# overallPCB.net
KiCad netlist of a schematic drawn in EAGLE
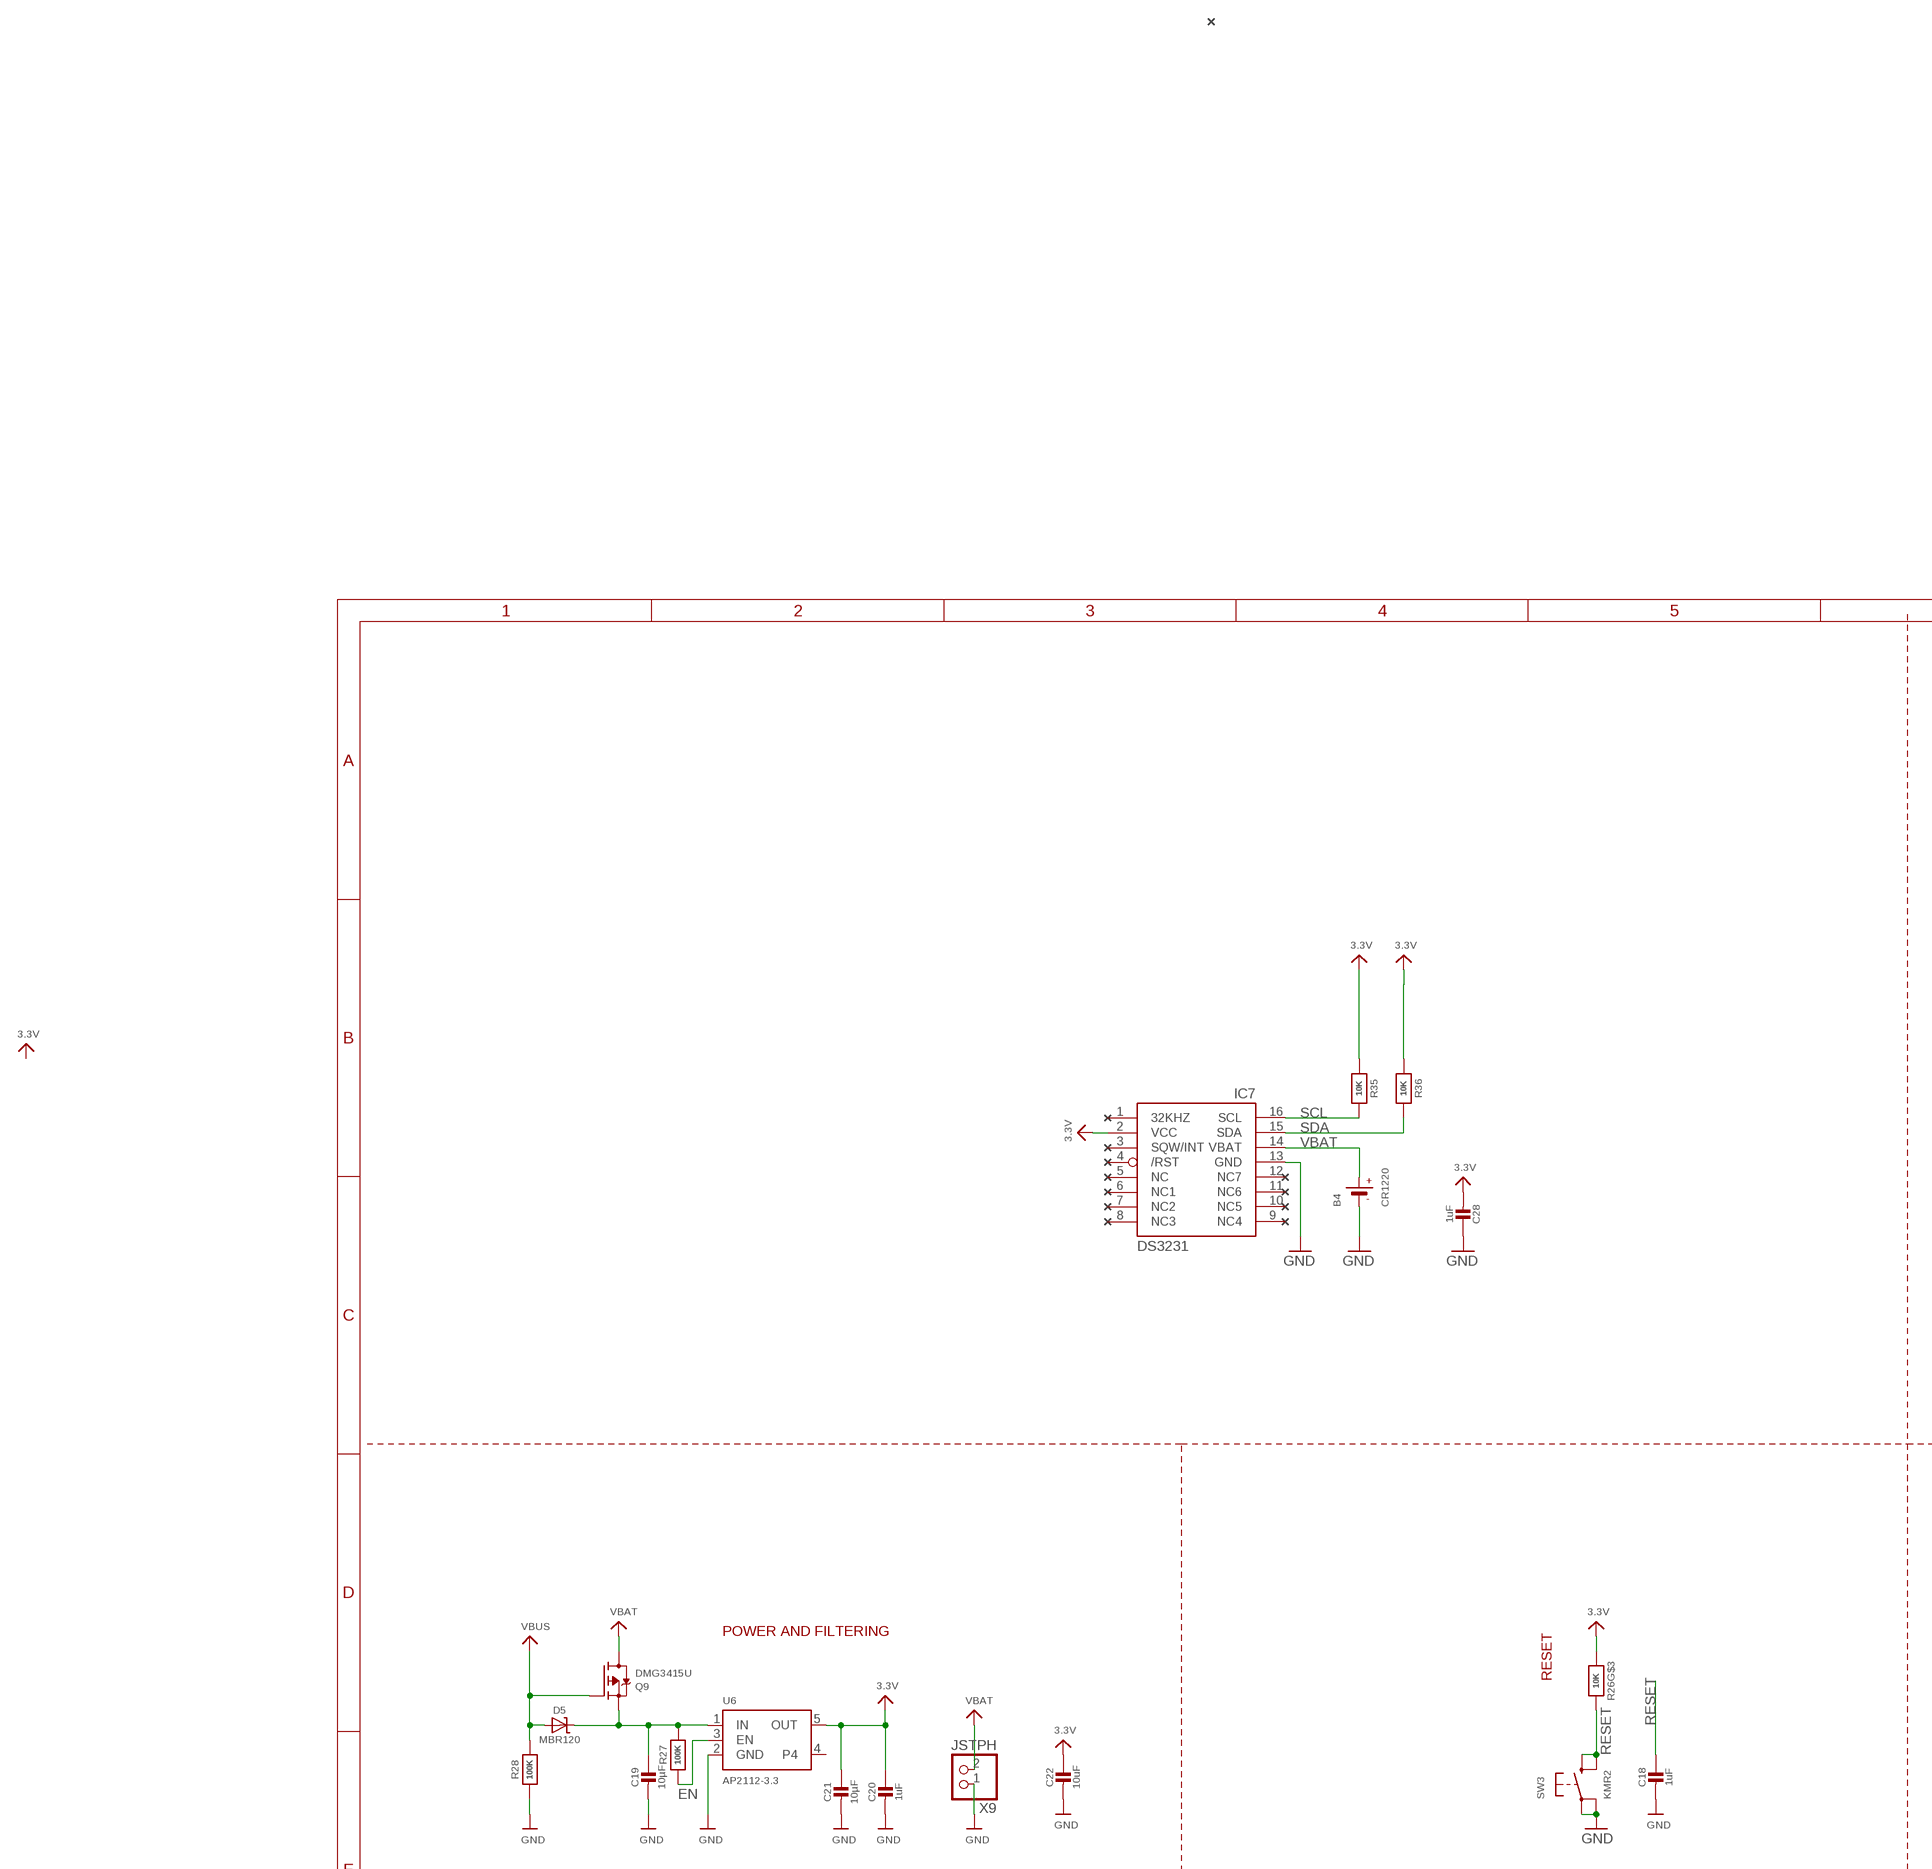
[diagram p0: schematic, sheet 1, part 1 of 3]
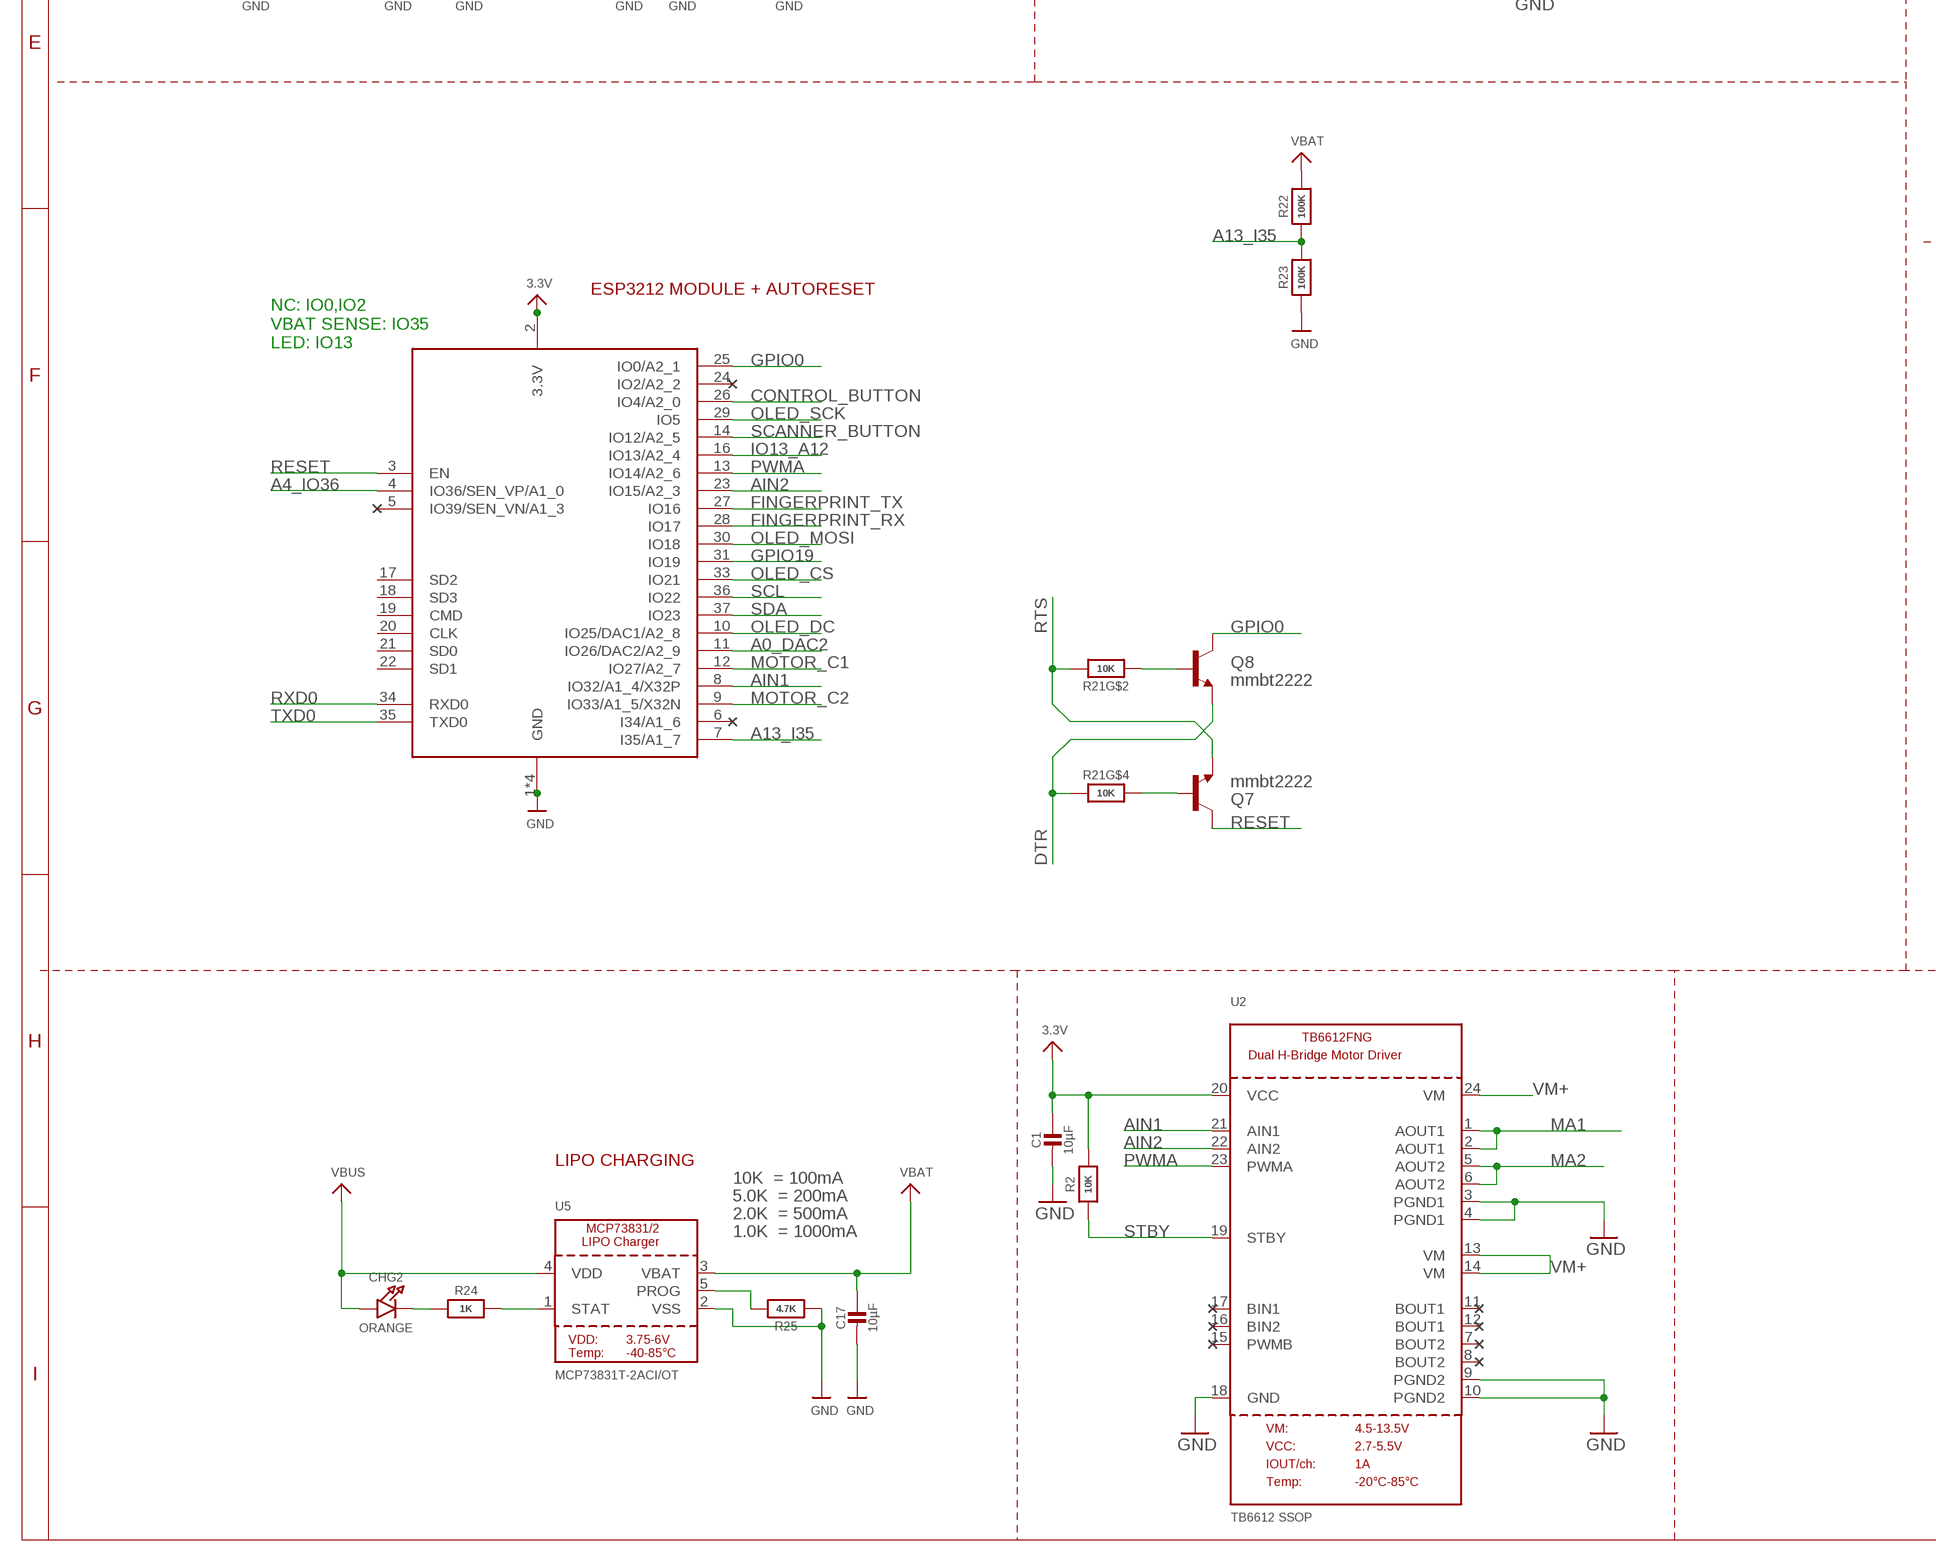
[diagram p1: schematic, sheet 1, part 2 of 3]
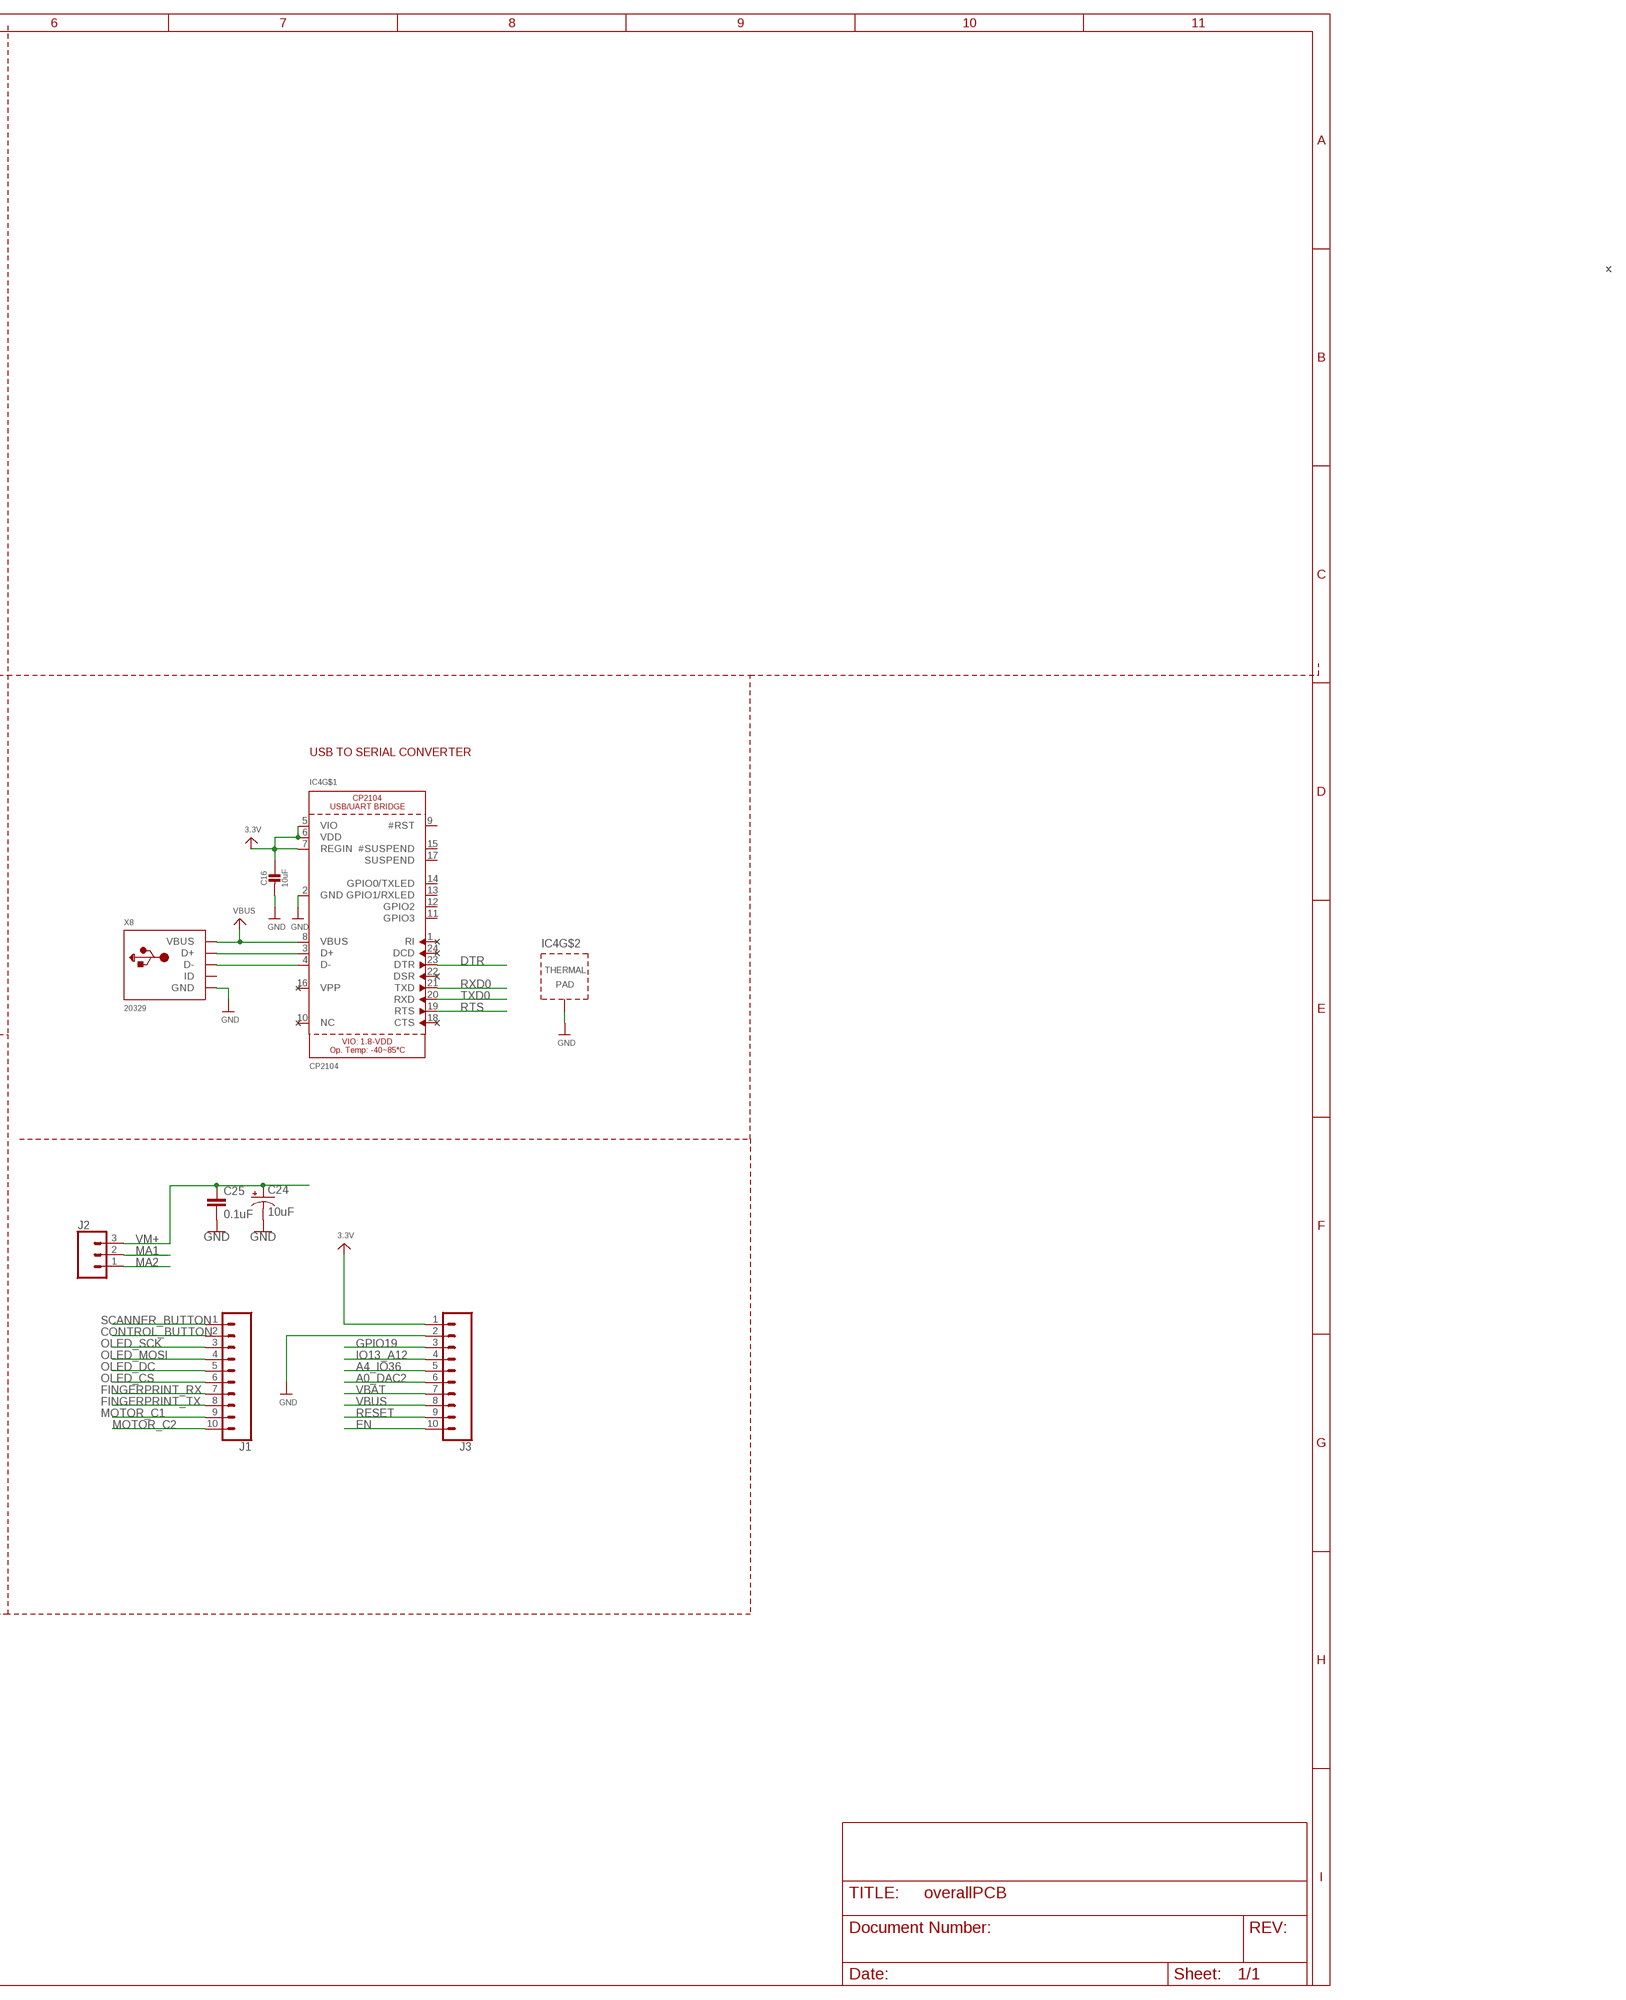
[diagram p2: schematic, sheet 1, part 3 of 3]

(export (version "E")
  (design (tool "Eeschema 10.0.6"))
  (components
    (comp (ref "B4")
      (value "CR1220")
      (footprint "eagle-import:CR1220")
      (libsource (lib "eagle-import") (part "BATTERYCR1220_SMT"))
    )
    (comp (ref "C1")
      (value "10µF")
      (footprint "eagle-import:0805-NO")
      (libsource (lib "eagle-import") (part "CAP_CERAMIC0805-NOOUTLINE"))
    )
    (comp (ref "C16")
      (value "10uF")
      (footprint "eagle-import:0805-NO")
      (libsource (lib "eagle-import") (part "CAP_CERAMIC0805-NOOUTLINE"))
    )
    (comp (ref "C17")
      (value "10µF")
      (footprint "eagle-import:0805-NO")
      (libsource (lib "eagle-import") (part "CAP_CERAMIC0805-NOOUTLINE"))
    )
    (comp (ref "C18")
      (value "1uF")
      (footprint "eagle-import:0603-NO")
      (libsource (lib "eagle-import") (part "CAP_CERAMIC0603_NO"))
    )
    (comp (ref "C19")
      (value "10µF")
      (footprint "eagle-import:0805-NO")
      (libsource (lib "eagle-import") (part "CAP_CERAMIC0805-NOOUTLINE"))
    )
    (comp (ref "C20")
      (value "1uF")
      (footprint "eagle-import:0603-NO")
      (libsource (lib "eagle-import") (part "CAP_CERAMIC0603_NO"))
    )
    (comp (ref "C21")
      (value "10µF")
      (footprint "eagle-import:0805-NO")
      (libsource (lib "eagle-import") (part "CAP_CERAMIC0805-NOOUTLINE"))
    )
    (comp (ref "C22")
      (value "10uF")
      (footprint "eagle-import:0805-NO")
      (libsource (lib "eagle-import") (part "CAP_CERAMIC0805-NOOUTLINE"))
    )
    (comp (ref "C24")
      (value "10uF")
      (footprint "eagle-import:EIA3216")
      (libsource (lib "eagle-import") (part "10UF-POLAR-EIA3216-16V-10%(TANT)"))
    )
    (comp (ref "C25")
      (value "0.1uF")
      (footprint "eagle-import:0402")
      (libsource (lib "eagle-import") (part "0.1UF-0402-16V-10%"))
    )
    (comp (ref "C28")
      (value "1uF")
      (footprint "eagle-import:0805-NO")
      (libsource (lib "eagle-import") (part "CAP_CERAMIC0805-NOOUTLINE"))
    )
    (comp (ref "CHG2")
      (value "ORANGE")
      (footprint "eagle-import:CHIPLED_0805_NOOUTLINE")
      (libsource (lib "eagle-import") (part "LED0805_NOOUTLINE"))
    )
    (comp (ref "D5")
      (value "MBR120")
      (footprint "eagle-import:SOD-123")
      (libsource (lib "eagle-import") (part "DIODE-SCHOTTKYSOD-123"))
    )
    (comp (ref "IC4")
      (value "CP2104")
      (footprint "eagle-import:QFN24_4MM_SMSC")
      (libsource (lib "eagle-import") (part "CP2104"))
    )
    (comp (ref "IC7")
      (value "DS3231/SO")
      (footprint "eagle-import:SO16W")
      (libsource (lib "eagle-import") (part "DS3231/SO"))
    )
    (comp (ref "J1")
      (value "CONN_10\"")
      (footprint "eagle-import:1X10")
      (libsource (lib "eagle-import") (part "CONN_10{dblquote}"))
    )
    (comp (ref "J2")
      (value "CONN_03POGO_PIN_HOLES_ONLY")
      (footprint "eagle-import:1X03_PP_HOLES_ONLY")
      (libsource (lib "eagle-import") (part "CONN_03POGO_PIN_HOLES_ONLY"))
    )
    (comp (ref "J3")
      (value "CONN_10\"")
      (footprint "eagle-import:1X10")
      (libsource (lib "eagle-import") (part "CONN_10{dblquote}"))
    )
    (comp (ref "Q7")
      (value "mmbt2222")
      (footprint "eagle-import:SOT23-3")
      (libsource (lib "eagle-import") (part "TRANSISTOR_NPNSOT23-3"))
    )
    (comp (ref "Q8")
      (value "mmbt2222")
      (footprint "eagle-import:SOT23-3")
      (libsource (lib "eagle-import") (part "TRANSISTOR_NPNSOT23-3"))
    )
    (comp (ref "Q9")
      (value "DMG3415U")
      (footprint "eagle-import:SOT23-R")
      (libsource (lib "eagle-import") (part "MOSFET-P"))
    )
    (comp (ref "R2")
      (value "10K")
      (footprint "eagle-import:0805-NO")
      (libsource (lib "eagle-import") (part "RESISTOR0805_NOOUTLINE"))
    )
    (comp (ref "R21")
      (value "10K")
      (footprint "eagle-import:RESPACK_4X0603")
      (libsource (lib "eagle-import") (part "RESISTOR_4PACK"))
    )
    (comp (ref "R22")
      (value "100K")
      (footprint "eagle-import:0603-NO")
      (libsource (lib "eagle-import") (part "RESISTOR_0603_NOOUT"))
    )
    (comp (ref "R23")
      (value "100K")
      (footprint "eagle-import:0603-NO")
      (libsource (lib "eagle-import") (part "RESISTOR_0603_NOOUT"))
    )
    (comp (ref "R24")
      (value "1K")
      (footprint "eagle-import:0603-NO")
      (libsource (lib "eagle-import") (part "RESISTOR_0603_NOOUT"))
    )
    (comp (ref "R25")
      (value "4.7K")
      (footprint "eagle-import:0603-NO")
      (libsource (lib "eagle-import") (part "RESISTOR_0603_NOOUT"))
    )
    (comp (ref "R26")
      (value "10K")
      (footprint "eagle-import:RESPACK_4X0603")
      (libsource (lib "eagle-import") (part "RESISTOR_4PACK"))
    )
    (comp (ref "R27")
      (value "100K")
      (footprint "eagle-import:0603-NO")
      (libsource (lib "eagle-import") (part "RESISTOR_0603_NOOUT"))
    )
    (comp (ref "R28")
      (value "100K")
      (footprint "eagle-import:0603-NO")
      (libsource (lib "eagle-import") (part "RESISTOR_0603_NOOUT"))
    )
    (comp (ref "R35")
      (value "10K")
      (footprint "eagle-import:0805-NO")
      (libsource (lib "eagle-import") (part "RESISTOR0805_NOOUTLINE"))
    )
    (comp (ref "R36")
      (value "10K")
      (footprint "eagle-import:0805-NO")
      (libsource (lib "eagle-import") (part "RESISTOR0805_NOOUTLINE"))
    )
    (comp (ref "SW3")
      (value "KMR2")
      (footprint "eagle-import:BTN_KMR2_4.6X2.8")
      (libsource (lib "eagle-import") (part "SWITCH_TACT_SMT4.6X2.8"))
    )
    (comp (ref "U2")
      (value "TB6612 SSOP")
      (footprint "eagle-import:SSOP24")
      (libsource (lib "eagle-import") (part "TB6612FNGSSOP"))
    )
    (comp (ref "U5")
      (value "MCP73831T-2ACI/OT")
      (footprint "eagle-import:SOT23-5")
      (libsource (lib "eagle-import") (part "MCP73831/2"))
    )
    (comp (ref "U6")
      (value "AP2112-3.3")
      (footprint "eagle-import:SOT23-5")
      (libsource (lib "eagle-import") (part "VREG_SOT23-5"))
    )
    (comp (ref "X7")
      (value "ESP32_WROOM32_SKINNY")
      (footprint "eagle-import:WROOM32_SKINNY")
      (libsource (lib "eagle-import") (part "ESP32_WROOM32_SKINNY"))
    )
    (comp (ref "X8")
      (value "20329")
      (footprint "eagle-import:4UCONN_20329_V2")
      (libsource (lib "eagle-import") (part "USB_MICRO_20329_V2"))
    )
    (comp (ref "X9")
      (value "JSTPH")
      (footprint "eagle-import:JSTPH2")
      (libsource (lib "eagle-import") (part "CON_JST_PH_2PIN"))
    )
  )
  (nets
    (net (code "1") (name "/A0_DAC2") (class "Default")
      (node (ref "J3") (pin "6") (pinfunction "6_6") (pintype "passive"))
      (node (ref "X7") (pin "11") (pinfunction "IO26/DAC2/A2_9_11") (pintype "bidirectional"))
    )
    (net (code "2") (name "/A4_IO36") (class "Default")
      (node (ref "J3") (pin "5") (pinfunction "5_5") (pintype "passive"))
      (node (ref "X7") (pin "4") (pinfunction "IO36/SEN_VP/A1_0_4") (pintype "passive"))
    )
    (net (code "3") (name "/A13_I35") (class "Default")
      (node (ref "R22") (pin "1") (pinfunction "1_1") (pintype "passive"))
      (node (ref "R23") (pin "2") (pinfunction "2_2") (pintype "passive"))
      (node (ref "X7") (pin "7") (pinfunction "I35/A1_7_7") (pintype "bidirectional"))
    )
    (net (code "4") (name "/AIN1") (class "Default")
      (node (ref "U2") (pin "21") (pinfunction "AIN1_21") (pintype "input"))
      (node (ref "X7") (pin "8") (pinfunction "IO32/A1_4/X32P_8") (pintype "bidirectional"))
    )
    (net (code "5") (name "/AIN2") (class "Default")
      (node (ref "U2") (pin "22") (pinfunction "AIN2_22") (pintype "input"))
      (node (ref "X7") (pin "23") (pinfunction "IO15/A2_3_23") (pintype "bidirectional"))
    )
    (net (code "6") (name "/CONTROL_BUTTON") (class "Default")
      (node (ref "J1") (pin "2") (pinfunction "2_2") (pintype "passive"))
      (node (ref "X7") (pin "26") (pinfunction "IO4/A2_0_26") (pintype "bidirectional"))
    )
    (net (code "7") (name "/DTR") (class "Default")
      (node (ref "IC4") (pin "23") (pinfunction "DTR_23") (pintype "output"))
      (node (ref "Q8") (pin "2") (pinfunction "E_2") (pintype "passive"))
      (node (ref "R21") (pin "4") (pinfunction "1_4") (pintype "passive"))
    )
    (net (code "8") (name "/EN") (class "Default")
      (node (ref "J3") (pin "10") (pinfunction "10_10") (pintype "passive"))
      (node (ref "R27") (pin "1") (pinfunction "1_1") (pintype "passive"))
      (node (ref "U6") (pin "3") (pinfunction "EN_3") (pintype "input"))
    )
    (net (code "9") (name "/FINGERPRINT_RX") (class "Default")
      (node (ref "J1") (pin "7") (pinfunction "7_7") (pintype "passive"))
      (node (ref "X7") (pin "28") (pinfunction "IO17_28") (pintype "bidirectional"))
    )
    (net (code "10") (name "/FINGERPRINT_TX") (class "Default")
      (node (ref "J1") (pin "8") (pinfunction "8_8") (pintype "passive"))
      (node (ref "X7") (pin "27") (pinfunction "IO16_27") (pintype "bidirectional"))
    )
    (net (code "11") (name "/GPIO0") (class "Default")
      (node (ref "Q8") (pin "3") (pinfunction "C_3") (pintype "passive"))
      (node (ref "X7") (pin "25") (pinfunction "IO0/A2_1_25") (pintype "bidirectional"))
    )
    (net (code "12") (name "/GPIO19") (class "Default")
      (node (ref "J3") (pin "3") (pinfunction "3_3") (pintype "passive"))
      (node (ref "X7") (pin "31") (pinfunction "IO19_31") (pintype "bidirectional"))
    )
    (net (code "13") (name "/IO13_A12") (class "Default")
      (node (ref "J3") (pin "4") (pinfunction "4_4") (pintype "passive"))
      (node (ref "X7") (pin "16") (pinfunction "IO13/A2_4_16") (pintype "bidirectional"))
    )
    (net (code "14") (name "/MA1") (class "Default")
      (node (ref "J2") (pin "2") (pinfunction "2_2") (pintype "passive"))
      (node (ref "U2") (pin "1") (pinfunction "AOUT1_1") (pintype "output"))
      (node (ref "U2") (pin "2") (pinfunction "AOUT1_2") (pintype "output"))
    )
    (net (code "15") (name "/MA2") (class "Default")
      (node (ref "J2") (pin "1") (pinfunction "1_1") (pintype "passive"))
      (node (ref "U2") (pin "5") (pinfunction "AOUT2_5") (pintype "output"))
      (node (ref "U2") (pin "6") (pinfunction "AOUT2_6") (pintype "output"))
    )
    (net (code "16") (name "/MOTOR_C1") (class "Default")
      (node (ref "J1") (pin "9") (pinfunction "9_9") (pintype "passive"))
      (node (ref "X7") (pin "12") (pinfunction "IO27/A2_7_12") (pintype "bidirectional"))
    )
    (net (code "17") (name "/MOTOR_C2") (class "Default")
      (node (ref "J1") (pin "10") (pinfunction "10_10") (pintype "passive"))
      (node (ref "X7") (pin "9") (pinfunction "IO33/A1_5/X32N_9") (pintype "bidirectional"))
    )
    (net (code "18") (name "/OLED_CS") (class "Default")
      (node (ref "J1") (pin "6") (pinfunction "6_6") (pintype "passive"))
      (node (ref "X7") (pin "33") (pinfunction "IO21_33") (pintype "bidirectional"))
    )
    (net (code "19") (name "/OLED_DC") (class "Default")
      (node (ref "J1") (pin "5") (pinfunction "5_5") (pintype "passive"))
      (node (ref "X7") (pin "10") (pinfunction "IO25/DAC1/A2_8_10") (pintype "bidirectional"))
    )
    (net (code "20") (name "/OLED_MOSI") (class "Default")
      (node (ref "J1") (pin "4") (pinfunction "4_4") (pintype "passive"))
      (node (ref "X7") (pin "30") (pinfunction "IO18_30") (pintype "bidirectional"))
    )
    (net (code "21") (name "/OLED_SCK") (class "Default")
      (node (ref "J1") (pin "3") (pinfunction "3_3") (pintype "passive"))
      (node (ref "X7") (pin "29") (pinfunction "IO5_29") (pintype "bidirectional"))
    )
    (net (code "22") (name "/PWMA") (class "Default")
      (node (ref "U2") (pin "23") (pinfunction "PWMA_23") (pintype "input"))
      (node (ref "X7") (pin "13") (pinfunction "IO14/A2_6_13") (pintype "bidirectional"))
    )
    (net (code "23") (name "/RESET") (class "Default")
      (node (ref "C18") (pin "1") (pinfunction "1_1") (pintype "passive"))
      (node (ref "J3") (pin "9") (pinfunction "9_9") (pintype "passive"))
      (node (ref "Q7") (pin "3") (pinfunction "C_3") (pintype "passive"))
      (node (ref "R26") (pin "6") (pinfunction "2_6") (pintype "passive"))
      (node (ref "SW3") (pin "B") (pinfunction "S_B") (pintype "passive"))
      (node (ref "SW3") (pin "B'") (pinfunction "S1_B'") (pintype "passive"))
      (node (ref "X7") (pin "3") (pinfunction "EN_3") (pintype "input"))
    )
    (net (code "24") (name "/RTS") (class "Default")
      (node (ref "IC4") (pin "19") (pinfunction "RTS_19") (pintype "output"))
      (node (ref "Q7") (pin "2") (pinfunction "E_2") (pintype "passive"))
      (node (ref "R21") (pin "7") (pinfunction "2_7") (pintype "passive"))
    )
    (net (code "25") (name "/RXD0") (class "Default")
      (node (ref "IC4") (pin "21") (pinfunction "TXD_21") (pintype "output"))
      (node (ref "X7") (pin "34") (pinfunction "RXD0_34") (pintype "input"))
    )
    (net (code "26") (name "/SCANNER_BUTTON") (class "Default")
      (node (ref "J1") (pin "1") (pinfunction "1_1") (pintype "passive"))
      (node (ref "X7") (pin "14") (pinfunction "IO12/A2_5_14") (pintype "bidirectional"))
    )
    (net (code "27") (name "/SCL") (class "Default")
      (node (ref "IC7") (pin "16") (pinfunction "SCL_16") (pintype "bidirectional"))
      (node (ref "R35") (pin "2") (pinfunction "2_2") (pintype "passive"))
      (node (ref "X7") (pin "36") (pinfunction "IO22_36") (pintype "bidirectional"))
    )
    (net (code "28") (name "/SDA") (class "Default")
      (node (ref "IC7") (pin "15") (pinfunction "SDA_15") (pintype "bidirectional"))
      (node (ref "R36") (pin "2") (pinfunction "2_2") (pintype "passive"))
      (node (ref "X7") (pin "37") (pinfunction "IO23_37") (pintype "bidirectional"))
    )
    (net (code "29") (name "/STBY") (class "Default")
      (node (ref "R2") (pin "1") (pinfunction "1_1") (pintype "passive"))
      (node (ref "U2") (pin "19") (pinfunction "STBY_19") (pintype "input"))
    )
    (net (code "30") (name "/TXD0") (class "Default")
      (node (ref "IC4") (pin "20") (pinfunction "RXD_20") (pintype "input"))
      (node (ref "X7") (pin "35") (pinfunction "TXD0_35") (pintype "output"))
    )
    (net (code "31") (name "/VM+") (class "Default")
      (node (ref "C24") (pin "+") (pinfunction "+_+") (pintype "passive"))
      (node (ref "C25") (pin "1") (pinfunction "1_1") (pintype "passive"))
      (node (ref "J2") (pin "3") (pinfunction "3_3") (pintype "passive"))
      (node (ref "U2") (pin "13") (pinfunction "VM_13") (pintype "power_in"))
      (node (ref "U2") (pin "14") (pinfunction "VM_14") (pintype "power_in"))
      (node (ref "U2") (pin "24") (pinfunction "VM_24") (pintype "power_in"))
    )
    (net (code "32") (name "3.3V") (class "Default")
      (node (ref "C1") (pin "1") (pinfunction "1_1") (pintype "passive"))
      (node (ref "C16") (pin "1") (pinfunction "1_1") (pintype "passive"))
      (node (ref "C20") (pin "1") (pinfunction "1_1") (pintype "passive"))
      (node (ref "C21") (pin "1") (pinfunction "1_1") (pintype "passive"))
      (node (ref "C22") (pin "1") (pinfunction "1_1") (pintype "passive"))
      (node (ref "C28") (pin "2") (pinfunction "2_2") (pintype "passive"))
      (node (ref "IC4") (pin "5") (pinfunction "VIO_5") (pintype "power_in"))
      (node (ref "IC4") (pin "6") (pinfunction "VDD_6") (pintype "power_in"))
      (node (ref "IC4") (pin "7") (pinfunction "REGIN_7") (pintype "power_in"))
      (node (ref "IC7") (pin "2") (pinfunction "VCC_2") (pintype "power_in"))
      (node (ref "J3") (pin "1") (pinfunction "1_1") (pintype "passive"))
      (node (ref "R2") (pin "2") (pinfunction "2_2") (pintype "passive"))
      (node (ref "R26") (pin "3") (pinfunction "1_3") (pintype "passive"))
      (node (ref "R35") (pin "1") (pinfunction "1_1") (pintype "passive"))
      (node (ref "R36") (pin "1") (pinfunction "1_1") (pintype "passive"))
      (node (ref "U2") (pin "20") (pinfunction "VCC_20") (pintype "power_in"))
      (node (ref "U6") (pin "5") (pinfunction "OUT_5") (pintype "power_in"))
      (node (ref "X7") (pin "2") (pinfunction "3.3V_2") (pintype "passive"))
    )
    (net (code "33") (name "GND") (class "Default")
      (node (ref "B4") (pin "-") (pinfunction "-_-") (pintype "passive"))
      (node (ref "C1") (pin "2") (pinfunction "2_2") (pintype "passive"))
      (node (ref "C16") (pin "2") (pinfunction "2_2") (pintype "passive"))
      (node (ref "C17") (pin "2") (pinfunction "2_2") (pintype "passive"))
      (node (ref "C18") (pin "2") (pinfunction "2_2") (pintype "passive"))
      (node (ref "C19") (pin "2") (pinfunction "2_2") (pintype "passive"))
      (node (ref "C20") (pin "2") (pinfunction "2_2") (pintype "passive"))
      (node (ref "C21") (pin "2") (pinfunction "2_2") (pintype "passive"))
      (node (ref "C22") (pin "2") (pinfunction "2_2") (pintype "passive"))
      (node (ref "C24") (pin "-") (pinfunction "-_-") (pintype "passive"))
      (node (ref "C25") (pin "2") (pinfunction "2_2") (pintype "passive"))
      (node (ref "C28") (pin "1") (pinfunction "1_1") (pintype "passive"))
      (node (ref "IC4") (pin "2") (pinfunction "GND_2") (pintype "power_in"))
      (node (ref "IC4") (pin "THERM") (pinfunction "TP_THERM") (pintype "power_in"))
      (node (ref "IC7") (pin "13") (pinfunction "GND_13") (pintype "power_in"))
      (node (ref "J3") (pin "2") (pinfunction "2_2") (pintype "passive"))
      (node (ref "R23") (pin "1") (pinfunction "1_1") (pintype "passive"))
      (node (ref "R25") (pin "1") (pinfunction "1_1") (pintype "passive"))
      (node (ref "R28") (pin "1") (pinfunction "1_1") (pintype "passive"))
      (node (ref "SW3") (pin "A") (pinfunction "P_A") (pintype "passive"))
      (node (ref "SW3") (pin "A'") (pinfunction "P1_A'") (pintype "passive"))
      (node (ref "U2") (pin "10") (pinfunction "PGND2_10") (pintype "power_in"))
      (node (ref "U2") (pin "18") (pinfunction "GND_18") (pintype "power_in"))
      (node (ref "U2") (pin "3") (pinfunction "PGND1_3") (pintype "power_in"))
      (node (ref "U2") (pin "4") (pinfunction "PGND1_4") (pintype "power_in"))
      (node (ref "U2") (pin "9") (pinfunction "PGND2_9") (pintype "power_in"))
      (node (ref "U5") (pin "2") (pinfunction "VSS_2") (pintype "power_in"))
      (node (ref "U6") (pin "2") (pinfunction "GND_2") (pintype "power_in"))
      (node (ref "X7") (pin "1") (pinfunction "GND_1") (pintype "passive"))
      (node (ref "X7") (pin "15") (pinfunction "GND_15") (pintype "passive"))
      (node (ref "X7") (pin "38") (pinfunction "GND_38") (pintype "passive"))
      (node (ref "X7") (pin "P$1") (pinfunction "GND_P$1") (pintype "passive"))
      (node (ref "X8") (pin "BASE@1") (pinfunction "GND_BASE@1") (pintype "power_in"))
      (node (ref "X8") (pin "BASE@2") (pinfunction "GND_BASE@2") (pintype "power_in"))
      (node (ref "X8") (pin "GND") (pinfunction "GND_GND") (pintype "power_in"))
      (node (ref "X8") (pin "SPRT@1") (pinfunction "GND_SPRT@1") (pintype "power_in"))
      (node (ref "X8") (pin "SPRT@2") (pinfunction "GND_SPRT@2") (pintype "power_in"))
      (node (ref "X8") (pin "SPRT@3") (pinfunction "GND_SPRT@3") (pintype "power_in"))
      (node (ref "X8") (pin "SPRT@4") (pinfunction "GND_SPRT@4") (pintype "power_in"))
      (node (ref "X9") (pin "1") (pinfunction "1_1") (pintype "passive"))
    )
    (net (code "34") (name "Net-(CHG2-PadC)") (class "Default")
      (node (ref "CHG2") (pin "C") (pinfunction "C_C") (pintype "passive"))
      (node (ref "R24") (pin "1") (pinfunction "1_1") (pintype "passive"))
    )
    (net (code "35") (name "Net-(IC4A-D+)") (class "Default")
      (node (ref "IC4") (pin "3") (pinfunction "D+_3") (pintype "bidirectional"))
      (node (ref "X8") (pin "D+") (pinfunction "D+_D+") (pintype "bidirectional"))
    )
    (net (code "36") (name "Net-(IC4A-D-)") (class "Default")
      (node (ref "IC4") (pin "4") (pinfunction "D-_4") (pintype "bidirectional"))
      (node (ref "X8") (pin "D-") (pinfunction "D-_D-") (pintype "bidirectional"))
    )
    (net (code "37") (name "Net-(Q7-B)") (class "Default")
      (node (ref "Q7") (pin "1") (pinfunction "B_1") (pintype "passive"))
      (node (ref "R21") (pin "5") (pinfunction "2_5") (pintype "passive"))
    )
    (net (code "38") (name "Net-(Q8-B)") (class "Default")
      (node (ref "Q8") (pin "1") (pinfunction "B_1") (pintype "passive"))
      (node (ref "R21") (pin "2") (pinfunction "1_2") (pintype "passive"))
    )
    (net (code "39") (name "Net-(Q9-S)") (class "Default")
      (node (ref "C19") (pin "1") (pinfunction "1_1") (pintype "passive"))
      (node (ref "D5") (pin "C") (pinfunction "C_C") (pintype "passive"))
      (node (ref "Q9") (pin "2") (pinfunction "S_2") (pintype "passive"))
      (node (ref "R27") (pin "2") (pinfunction "2_2") (pintype "passive"))
      (node (ref "U6") (pin "1") (pinfunction "IN_1") (pintype "power_in"))
    )
    (net (code "40") (name "Net-(U5-PROG)") (class "Default")
      (node (ref "R25") (pin "2") (pinfunction "2_2") (pintype "passive"))
      (node (ref "U5") (pin "5") (pinfunction "PROG_5") (pintype "input"))
    )
    (net (code "41") (name "Net-(U5-STAT)") (class "Default")
      (node (ref "R24") (pin "2") (pinfunction "2_2") (pintype "passive"))
      (node (ref "U5") (pin "1") (pinfunction "STAT_1") (pintype "output"))
    )
    (net (code "42") (name "VBAT") (class "Default")
      (node (ref "B4") (pin "+$1") (pinfunction "+_+$1") (pintype "passive"))
      (node (ref "C17") (pin "1") (pinfunction "1_1") (pintype "passive"))
      (node (ref "IC7") (pin "14") (pinfunction "VBAT_14") (pintype "power_in"))
      (node (ref "J3") (pin "7") (pinfunction "7_7") (pintype "passive"))
      (node (ref "Q9") (pin "3") (pinfunction "D_3") (pintype "passive"))
      (node (ref "R22") (pin "2") (pinfunction "2_2") (pintype "passive"))
      (node (ref "U5") (pin "3") (pinfunction "VBAT_3") (pintype "power_in"))
      (node (ref "X9") (pin "2") (pinfunction "2_2") (pintype "passive"))
    )
    (net (code "43") (name "VBUS") (class "Default")
      (node (ref "CHG2") (pin "A") (pinfunction "A_A") (pintype "passive"))
      (node (ref "D5") (pin "A") (pinfunction "A_A") (pintype "passive"))
      (node (ref "IC4") (pin "8") (pinfunction "VBUS_8") (pintype "power_in"))
      (node (ref "J3") (pin "8") (pinfunction "8_8") (pintype "passive"))
      (node (ref "Q9") (pin "1") (pinfunction "G_1") (pintype "passive"))
      (node (ref "R28") (pin "2") (pinfunction "2_2") (pintype "passive"))
      (node (ref "U5") (pin "4") (pinfunction "VDD_4") (pintype "power_in"))
      (node (ref "X8") (pin "VBUS") (pinfunction "VBUS_VBUS") (pintype "power_in"))
    )
    (net (code "44") (name "unconnected-(IC4A-#RST-Pad9)") (class "Default")
      (node (ref "IC4") (pin "9") (pinfunction "#RST_9") (pintype "bidirectional"))
    )
    (net (code "45") (name "unconnected-(IC4A-#SUSPEND-Pad15)") (class "Default")
      (node (ref "IC4") (pin "15") (pinfunction "#SUSPEND_15") (pintype "output"))
    )
    (net (code "46") (name "unconnected-(IC4A-CTS-Pad18)") (class "Default")
      (node (ref "IC4") (pin "18") (pinfunction "CTS_18") (pintype "input"))
    )
    (net (code "47") (name "unconnected-(IC4A-DCD-Pad24)") (class "Default")
      (node (ref "IC4") (pin "24") (pinfunction "DCD_24") (pintype "input"))
    )
    (net (code "48") (name "unconnected-(IC4A-DSR-Pad22)") (class "Default")
      (node (ref "IC4") (pin "22") (pinfunction "DSR_22") (pintype "input"))
    )
    (net (code "49") (name "unconnected-(IC4A-GPIO0{slash}TXLED-Pad14)") (class "Default")
      (node (ref "IC4") (pin "14") (pinfunction "GPIO0/TXLED_14") (pintype "bidirectional"))
    )
    (net (code "50") (name "unconnected-(IC4A-GPIO1{slash}RXLED-Pad13)") (class "Default")
      (node (ref "IC4") (pin "13") (pinfunction "GPIO1/RXLED_13") (pintype "bidirectional"))
    )
    (net (code "51") (name "unconnected-(IC4A-GPIO2-Pad12)") (class "Default")
      (node (ref "IC4") (pin "12") (pinfunction "GPIO2_12") (pintype "bidirectional"))
    )
    (net (code "52") (name "unconnected-(IC4A-GPIO3-Pad11)") (class "Default")
      (node (ref "IC4") (pin "11") (pinfunction "GPIO3_11") (pintype "bidirectional"))
    )
    (net (code "53") (name "unconnected-(IC4A-NC-Pad10)") (class "Default")
      (node (ref "IC4") (pin "10") (pinfunction "NC_10") (pintype "no_connect"))
    )
    (net (code "54") (name "unconnected-(IC4A-RI-Pad1)") (class "Default")
      (node (ref "IC4") (pin "1") (pinfunction "RI_1") (pintype "input"))
    )
    (net (code "55") (name "unconnected-(IC4A-SUSPEND-Pad17)") (class "Default")
      (node (ref "IC4") (pin "17") (pinfunction "SUSPEND_17") (pintype "output"))
    )
    (net (code "56") (name "unconnected-(IC4A-VPP-Pad16)") (class "Default")
      (node (ref "IC4") (pin "16") (pinfunction "VPP_16") (pintype "bidirectional"))
    )
    (net (code "57") (name "unconnected-(IC7-32KHZ-Pad1)") (class "Default")
      (node (ref "IC7") (pin "1") (pinfunction "32KHZ_1") (pintype "output"))
    )
    (net (code "58") (name "unconnected-(IC7-NC-Pad5)") (class "Default")
      (node (ref "IC7") (pin "5") (pinfunction "NC_5") (pintype "no_connect"))
    )
    (net (code "59") (name "unconnected-(IC7-NC1-Pad6)") (class "Default")
      (node (ref "IC7") (pin "6") (pinfunction "NC1_6") (pintype "no_connect"))
    )
    (net (code "60") (name "unconnected-(IC7-NC2-Pad7)") (class "Default")
      (node (ref "IC7") (pin "7") (pinfunction "NC2_7") (pintype "no_connect"))
    )
    (net (code "61") (name "unconnected-(IC7-NC3-Pad8)") (class "Default")
      (node (ref "IC7") (pin "8") (pinfunction "NC3_8") (pintype "no_connect"))
    )
    (net (code "62") (name "unconnected-(IC7-NC4-Pad9)") (class "Default")
      (node (ref "IC7") (pin "9") (pinfunction "NC4_9") (pintype "no_connect"))
    )
    (net (code "63") (name "unconnected-(IC7-NC5-Pad10)") (class "Default")
      (node (ref "IC7") (pin "10") (pinfunction "NC5_10") (pintype "no_connect"))
    )
    (net (code "64") (name "unconnected-(IC7-NC6-Pad11)") (class "Default")
      (node (ref "IC7") (pin "11") (pinfunction "NC6_11") (pintype "no_connect"))
    )
    (net (code "65") (name "unconnected-(IC7-NC7-Pad12)") (class "Default")
      (node (ref "IC7") (pin "12") (pinfunction "NC7_12") (pintype "no_connect"))
    )
    (net (code "66") (name "unconnected-(IC7-SQW{slash}INT-Pad3)") (class "Default")
      (node (ref "IC7") (pin "3") (pinfunction "SQW/INT_3") (pintype "output"))
    )
    (net (code "67") (name "unconnected-(IC7-{slash}RST-Pad4)") (class "Default")
      (node (ref "IC7") (pin "4") (pinfunction "/RST_4") (pintype "passive"))
    )
    (net (code "68") (name "unconnected-(U2-BIN1-Pad17)") (class "Default")
      (node (ref "U2") (pin "17") (pinfunction "BIN1_17") (pintype "input"))
    )
    (net (code "69") (name "unconnected-(U2-BIN2-Pad16)") (class "Default")
      (node (ref "U2") (pin "16") (pinfunction "BIN2_16") (pintype "input"))
    )
    (net (code "70") (name "unconnected-(U2-BOUT1-Pad11)") (class "Default")
      (node (ref "U2") (pin "11") (pinfunction "BOUT1_11") (pintype "output"))
    )
    (net (code "71") (name "unconnected-(U2-BOUT1-Pad12)") (class "Default")
      (node (ref "U2") (pin "12") (pinfunction "BOUT1_12") (pintype "output"))
    )
    (net (code "72") (name "unconnected-(U2-BOUT2-Pad7)") (class "Default")
      (node (ref "U2") (pin "7") (pinfunction "BOUT2_7") (pintype "output"))
    )
    (net (code "73") (name "unconnected-(U2-BOUT2-Pad8)") (class "Default")
      (node (ref "U2") (pin "8") (pinfunction "BOUT2_8") (pintype "output"))
    )
    (net (code "74") (name "unconnected-(U2-PWMB-Pad15)") (class "Default")
      (node (ref "U2") (pin "15") (pinfunction "PWMB_15") (pintype "input"))
    )
    (net (code "75") (name "unconnected-(U6-P4-Pad4)") (class "Default")
      (node (ref "U6") (pin "4") (pinfunction "P4_4") (pintype "bidirectional"))
    )
    (net (code "76") (name "unconnected-(X7-CLK-Pad20)") (class "Default")
      (node (ref "X7") (pin "20") (pinfunction "CLK_20") (pintype "bidirectional"))
    )
    (net (code "77") (name "unconnected-(X7-CMD-Pad19)") (class "Default")
      (node (ref "X7") (pin "19") (pinfunction "CMD_19") (pintype "bidirectional"))
    )
    (net (code "78") (name "unconnected-(X7-I34{slash}A1_6-Pad6)") (class "Default")
      (node (ref "X7") (pin "6") (pinfunction "I34/A1_6_6") (pintype "bidirectional"))
    )
    (net (code "79") (name "unconnected-(X7-IO2{slash}A2_2-Pad24)") (class "Default")
      (node (ref "X7") (pin "24") (pinfunction "IO2/A2_2_24") (pintype "bidirectional"))
    )
    (net (code "80") (name "unconnected-(X7-IO39{slash}SEN_VN{slash}A1_3-Pad5)") (class "Default")
      (node (ref "X7") (pin "5") (pinfunction "IO39/SEN_VN/A1_3_5") (pintype "passive"))
    )
    (net (code "81") (name "unconnected-(X7-SD0-Pad21)") (class "Default")
      (node (ref "X7") (pin "21") (pinfunction "SD0_21") (pintype "bidirectional"))
    )
    (net (code "82") (name "unconnected-(X7-SD1-Pad22)") (class "Default")
      (node (ref "X7") (pin "22") (pinfunction "SD1_22") (pintype "bidirectional"))
    )
    (net (code "83") (name "unconnected-(X7-SD2-Pad17)") (class "Default")
      (node (ref "X7") (pin "17") (pinfunction "SD2_17") (pintype "bidirectional"))
    )
    (net (code "84") (name "unconnected-(X7-SD3-Pad18)") (class "Default")
      (node (ref "X7") (pin "18") (pinfunction "SD3_18") (pintype "bidirectional"))
    )
    (net (code "85") (name "unconnected-(X8-PadID)") (class "Default")
      (node (ref "X8") (pin "ID") (pinfunction "ID_ID") (pintype "bidirectional"))
    )
  )
)
